# Control_Board.net
KiCad netlist of a schematic drawn in EAGLE
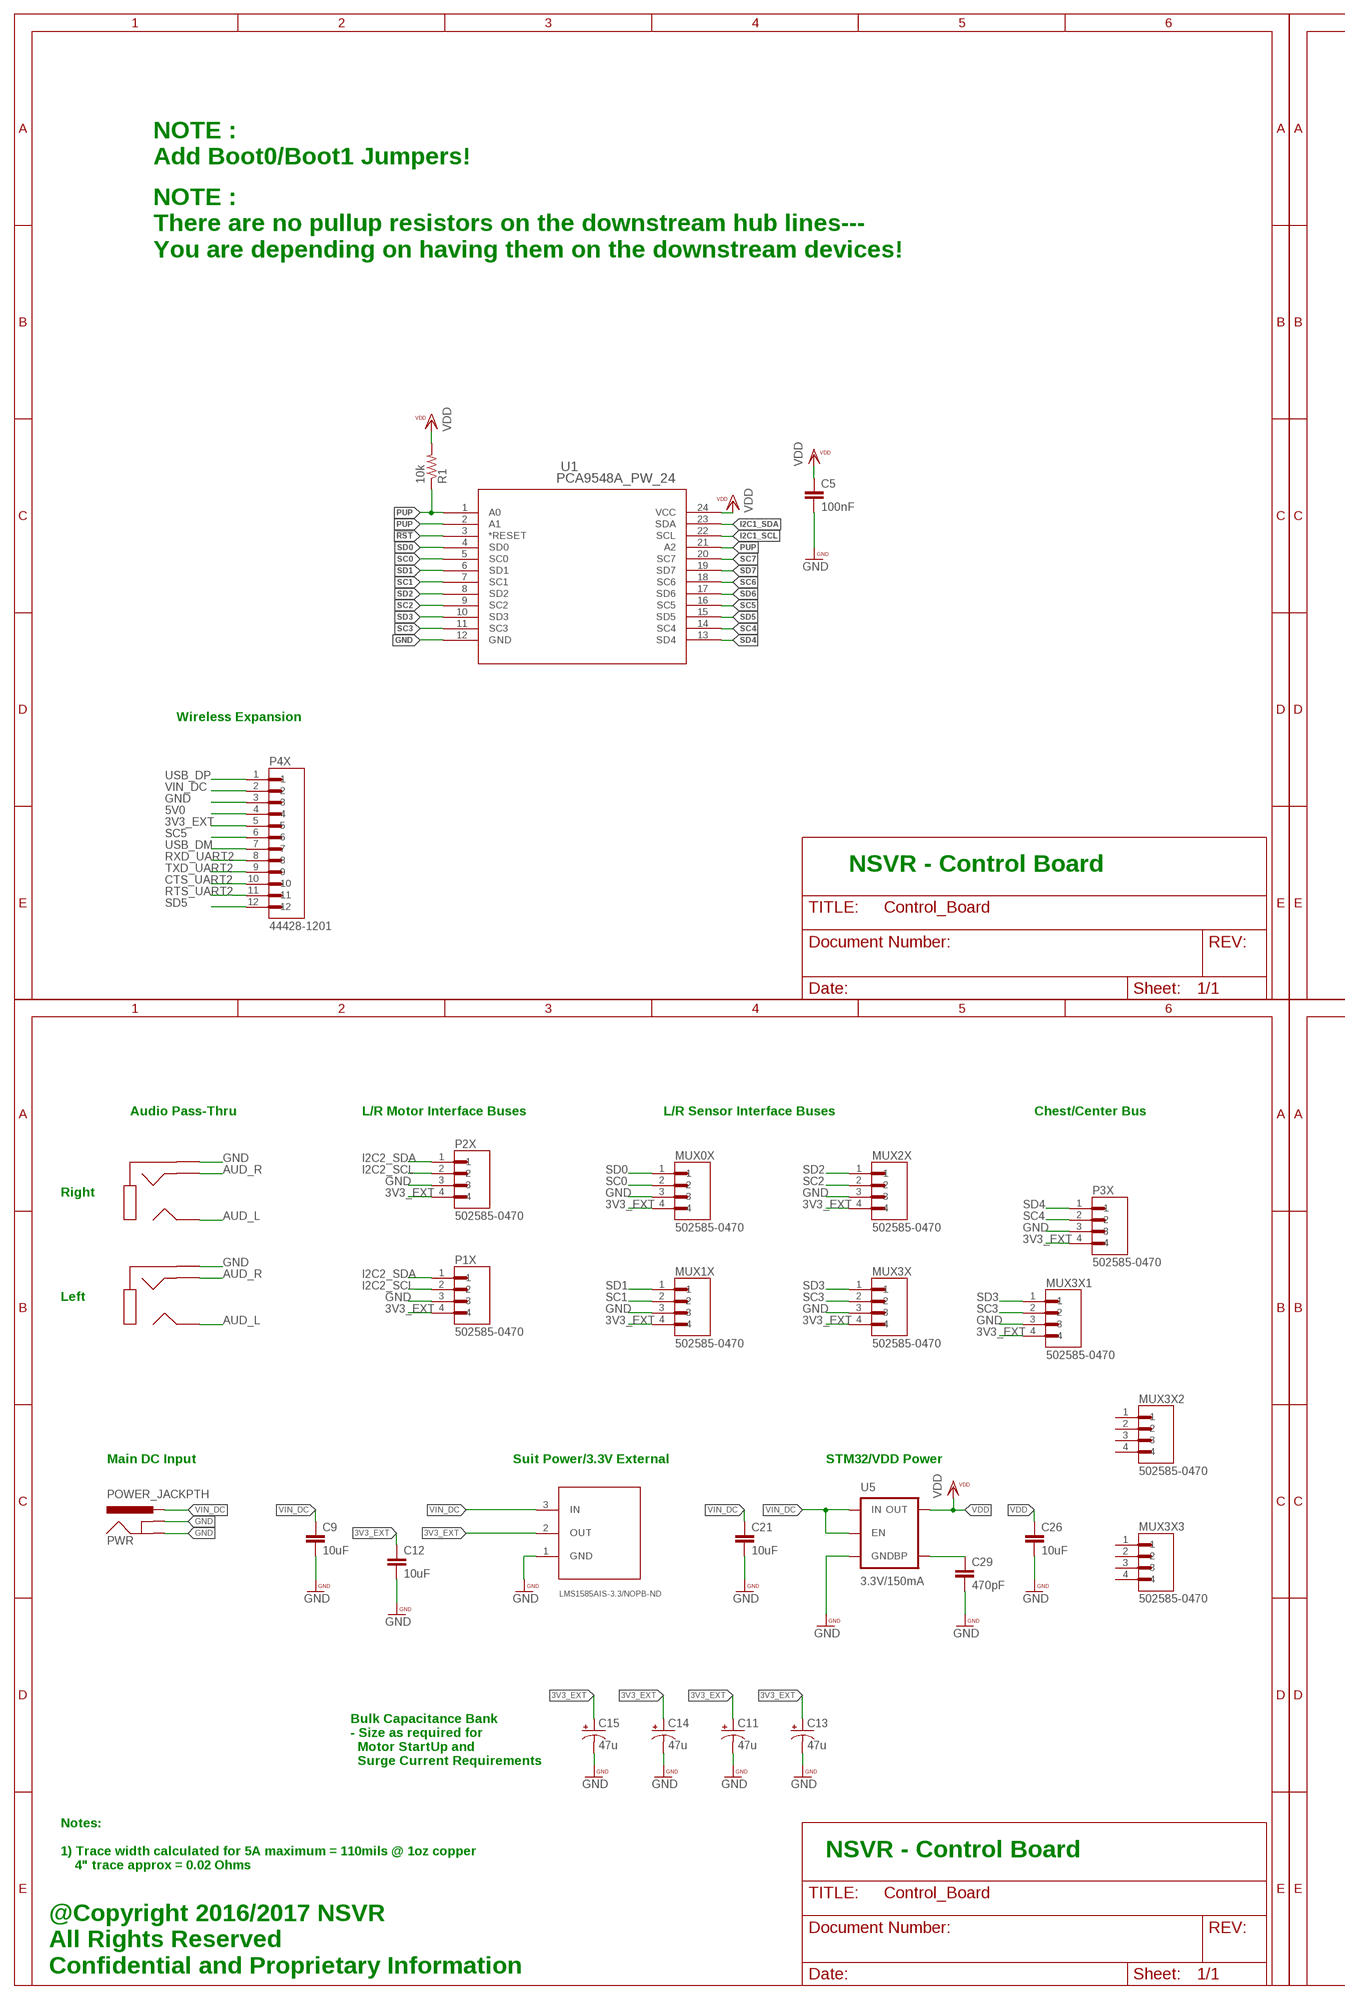
[diagram p0: schematic, sheet 1, part 1 of 2]
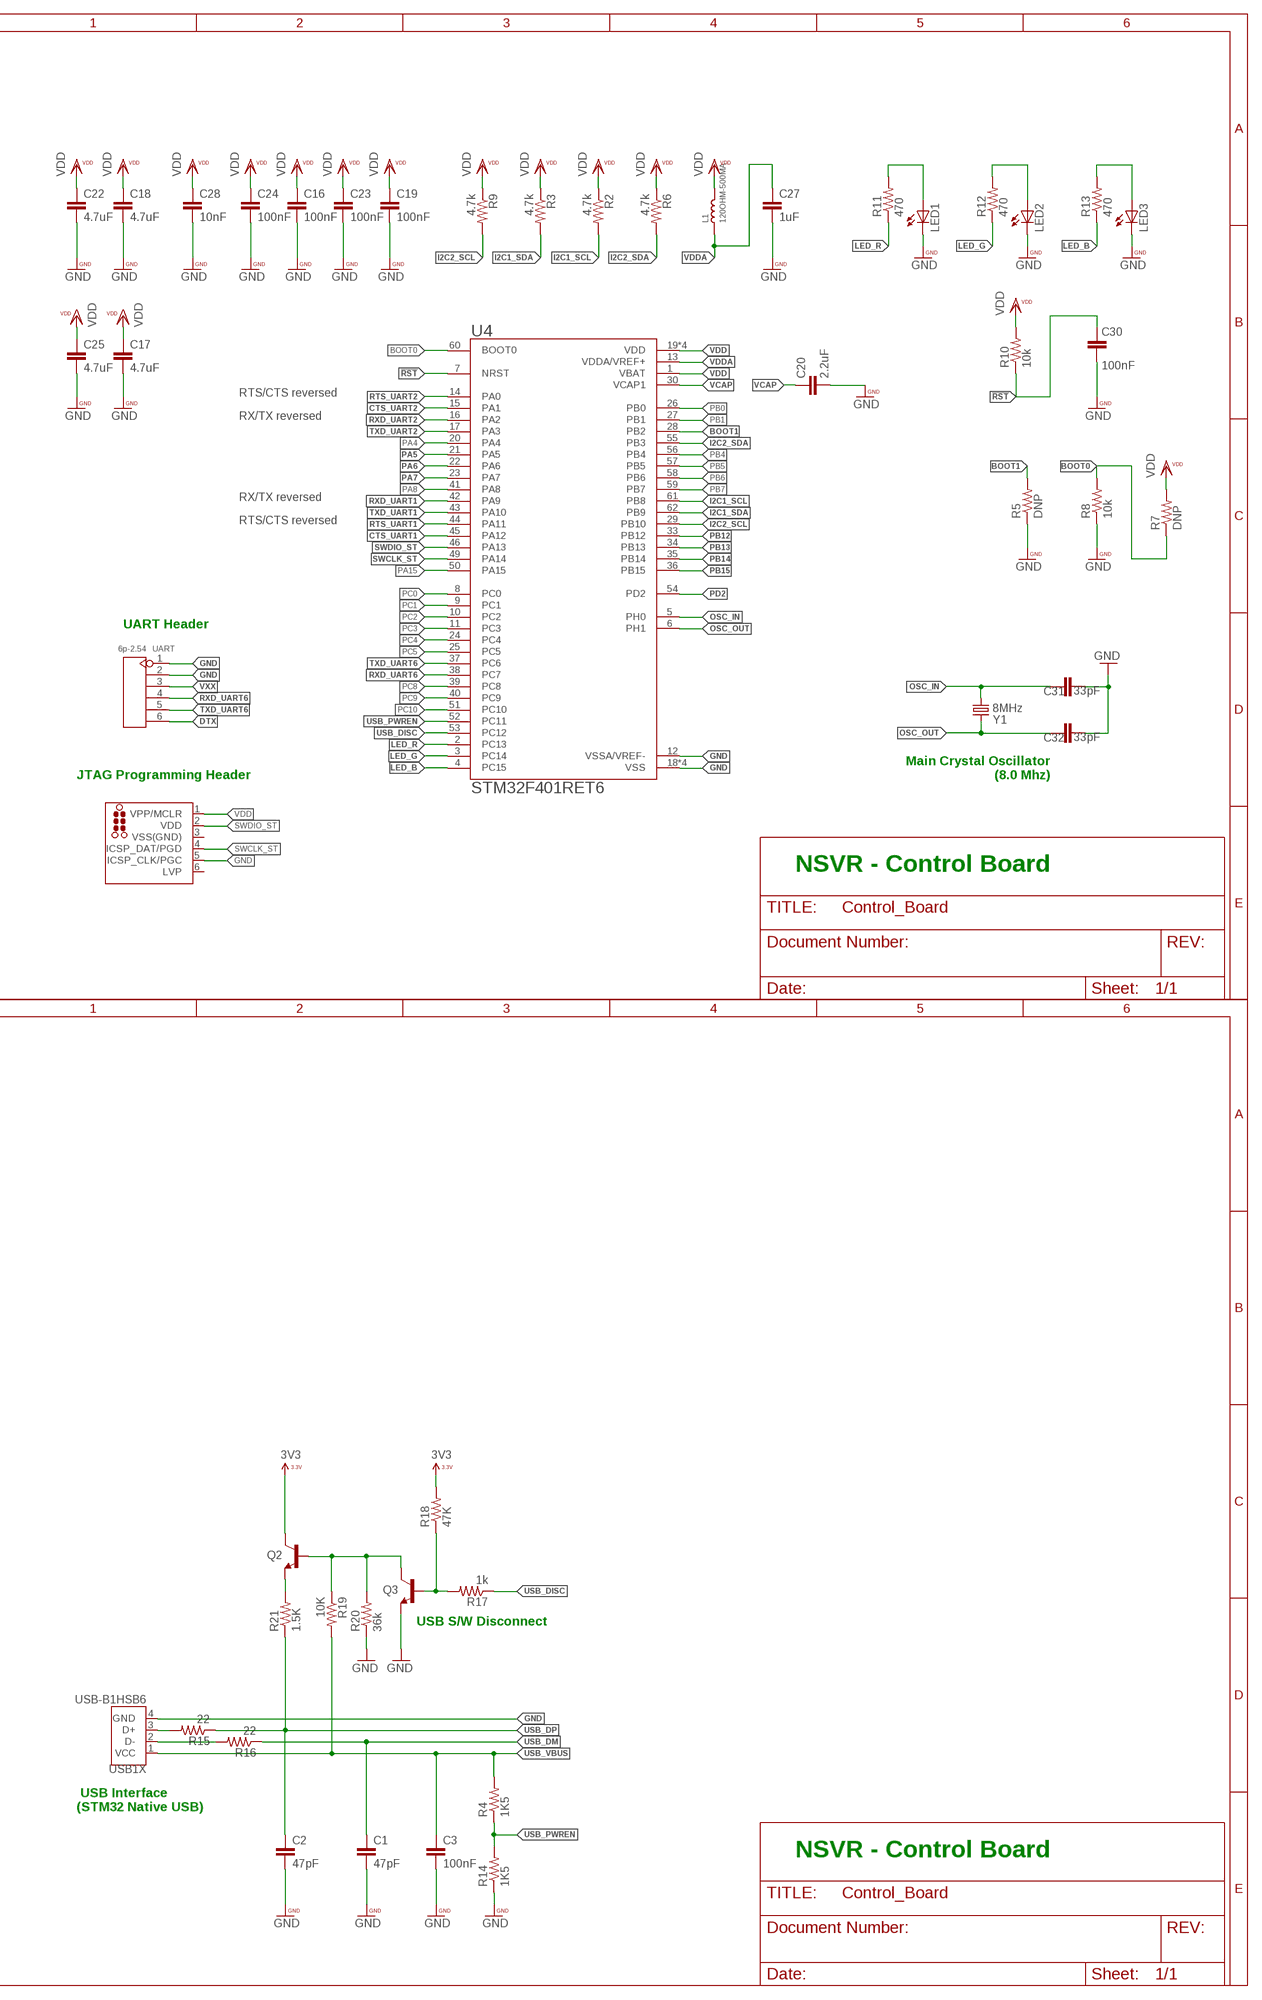
[diagram p1: schematic, sheet 1, part 2 of 2]

(export (version "E")
  (design (tool "Eeschema 10.0.6"))
  (components
    (comp (ref "C1")
      (value "47pF")
      (footprint "eagle-import:0402-CAP")
      (libsource (lib "eagle-import") (part "CAP0402-CAP"))
    )
    (comp (ref "C2")
      (value "47pF")
      (footprint "eagle-import:0402-CAP")
      (libsource (lib "eagle-import") (part "CAP0402-CAP"))
    )
    (comp (ref "C3")
      (value "100nF")
      (footprint "eagle-import:0402-CAP")
      (libsource (lib "eagle-import") (part "CAP0402-CAP"))
    )
    (comp (ref "C5")
      (value "100nF")
      (footprint "eagle-import:0402-CAP")
      (libsource (lib "eagle-import") (part "CAP0402-CAP"))
    )
    (comp (ref "C9")
      (value "10uF")
      (footprint "eagle-import:0603-CAP")
      (libsource (lib "eagle-import") (part "CAP0603-CAP"))
    )
    (comp (ref "C11")
      (value "47u")
      (footprint "eagle-import:PANASONIC_D")
      (libsource (lib "eagle-import") (part "CAP_POLD"))
    )
    (comp (ref "C12")
      (value "10uF")
      (footprint "eagle-import:0603-CAP")
      (libsource (lib "eagle-import") (part "CAP0603-CAP"))
    )
    (comp (ref "C13")
      (value "47u")
      (footprint "eagle-import:PANASONIC_D")
      (libsource (lib "eagle-import") (part "CAP_POLD"))
    )
    (comp (ref "C14")
      (value "47u")
      (footprint "eagle-import:PANASONIC_D")
      (libsource (lib "eagle-import") (part "CAP_POLD"))
    )
    (comp (ref "C15")
      (value "47u")
      (footprint "eagle-import:PANASONIC_D")
      (libsource (lib "eagle-import") (part "CAP_POLD"))
    )
    (comp (ref "C16")
      (value "100nF")
      (footprint "eagle-import:0402-CAP")
      (libsource (lib "eagle-import") (part "CAP0402-CAP"))
    )
    (comp (ref "C17")
      (value "4.7uF")
      (footprint "eagle-import:0402-CAP")
      (libsource (lib "eagle-import") (part "CAP0402-CAP"))
    )
    (comp (ref "C18")
      (value "4.7uF")
      (footprint "eagle-import:0402-CAP")
      (libsource (lib "eagle-import") (part "CAP0402-CAP"))
    )
    (comp (ref "C19")
      (value "100nF")
      (footprint "eagle-import:0402-CAP")
      (libsource (lib "eagle-import") (part "CAP0402-CAP"))
    )
    (comp (ref "C20")
      (value "2.2uF")
      (footprint "eagle-import:0402-CAP")
      (libsource (lib "eagle-import") (part "CAP0402-CAP"))
    )
    (comp (ref "C21")
      (value "10uF")
      (footprint "eagle-import:0603-CAP")
      (libsource (lib "eagle-import") (part "CAP0603-CAP"))
    )
    (comp (ref "C22")
      (value "4.7uF")
      (footprint "eagle-import:0402-CAP")
      (libsource (lib "eagle-import") (part "CAP0402-CAP"))
    )
    (comp (ref "C23")
      (value "100nF")
      (footprint "eagle-import:0402-CAP")
      (libsource (lib "eagle-import") (part "CAP0402-CAP"))
    )
    (comp (ref "C24")
      (value "100nF")
      (footprint "eagle-import:0402-CAP")
      (libsource (lib "eagle-import") (part "CAP0402-CAP"))
    )
    (comp (ref "C25")
      (value "4.7uF")
      (footprint "eagle-import:0402-CAP")
      (libsource (lib "eagle-import") (part "CAP0402-CAP"))
    )
    (comp (ref "C26")
      (value "10uF")
      (footprint "eagle-import:0603-CAP")
      (libsource (lib "eagle-import") (part "CAP0603-CAP"))
    )
    (comp (ref "C27")
      (value "1uF")
      (footprint "eagle-import:0402-CAP")
      (libsource (lib "eagle-import") (part "CAP0402-CAP"))
    )
    (comp (ref "C28")
      (value "10nF")
      (footprint "eagle-import:0402-CAP")
      (libsource (lib "eagle-import") (part "CAP0402-CAP"))
    )
    (comp (ref "C29")
      (value "470pF")
      (footprint "eagle-import:0402-CAP")
      (libsource (lib "eagle-import") (part "CAP0402-CAP"))
    )
    (comp (ref "C30")
      (value "100nF")
      (footprint "eagle-import:0402-CAP")
      (libsource (lib "eagle-import") (part "CAP0402-CAP"))
    )
    (comp (ref "C31")
      (value "33pF")
      (footprint "eagle-import:0402-CAP")
      (libsource (lib "eagle-import") (part "CAP0402-CAP"))
    )
    (comp (ref "C32")
      (value "33pF")
      (footprint "eagle-import:0402-CAP")
      (libsource (lib "eagle-import") (part "CAP0402-CAP"))
    )
    (comp (ref "J_ST")
      (value "TC2030-MCP-NL")
      (footprint "eagle-import:TC2030-MCP-NL")
      (libsource (lib "eagle-import") (part "TC2030-MCP-NL"))
    )
    (comp (ref "L1")
      (value "120OHM-500MA")
      (footprint "eagle-import:L0603")
      (fields (field (name "MPN") "BLM18AG121SN1D"))
      (libsource (lib "eagle-import") (part "SMD-FERRITE-CHIP-120-OHM-500MA(0603)"))
    )
    (comp (ref "LED1")
      (value "LEDCHIP-LED0603")
      (footprint "eagle-import:CHIP-LED0603")
      (libsource (lib "eagle-import") (part "LEDCHIP-LED0603"))
    )
    (comp (ref "LED2")
      (value "LEDCHIP-LED0603")
      (footprint "eagle-import:CHIP-LED0603")
      (libsource (lib "eagle-import") (part "LEDCHIP-LED0603"))
    )
    (comp (ref "LED3")
      (value "LEDCHIP-LED0603")
      (footprint "eagle-import:CHIP-LED0603")
      (libsource (lib "eagle-import") (part "LEDCHIP-LED0603"))
    )
    (comp (ref "MUX0X")
      (value "502585-0470")
      (footprint "eagle-import:MOLEX_502585-0470")
      (fields (field (name "MF") "Molex"))
      (libsource (lib "eagle-import") (part "502585-0470"))
    )
    (comp (ref "MUX1X")
      (value "502585-0470")
      (footprint "eagle-import:MOLEX_502585-0470")
      (fields (field (name "MF") "Molex"))
      (libsource (lib "eagle-import") (part "502585-0470"))
    )
    (comp (ref "MUX2X")
      (value "502585-0470")
      (footprint "eagle-import:MOLEX_502585-0470")
      (fields (field (name "MF") "Molex"))
      (libsource (lib "eagle-import") (part "502585-0470"))
    )
    (comp (ref "MUX3X")
      (value "502585-0470")
      (footprint "eagle-import:MOLEX_502585-0470")
      (fields (field (name "MF") "Molex"))
      (libsource (lib "eagle-import") (part "502585-0470"))
    )
    (comp (ref "MUX3X1")
      (value "502585-0470")
      (footprint "eagle-import:MOLEX_502585-0470")
      (fields (field (name "MF") "Molex"))
      (libsource (lib "eagle-import") (part "502585-0470"))
    )
    (comp (ref "MUX3X2")
      (value "502585-0470")
      (footprint "eagle-import:MOLEX_502585-0470")
      (fields (field (name "MF") "Molex"))
      (libsource (lib "eagle-import") (part "502585-0470"))
    )
    (comp (ref "MUX3X3")
      (value "502585-0470")
      (footprint "eagle-import:MOLEX_502585-0470")
      (fields (field (name "MF") "Molex"))
      (libsource (lib "eagle-import") (part "502585-0470"))
    )
    (comp (ref "P1X")
      (value "502585-0470")
      (footprint "eagle-import:MOLEX_502585-0470")
      (fields (field (name "MF") "Molex"))
      (libsource (lib "eagle-import") (part "502585-0470"))
    )
    (comp (ref "P2X")
      (value "502585-0470")
      (footprint "eagle-import:MOLEX_502585-0470")
      (fields (field (name "MF") "Molex"))
      (libsource (lib "eagle-import") (part "502585-0470"))
    )
    (comp (ref "P3X")
      (value "502585-0470")
      (footprint "eagle-import:MOLEX_502585-0470")
      (fields (field (name "MF") "Molex"))
      (libsource (lib "eagle-import") (part "502585-0470"))
    )
    (comp (ref "P4X")
      (value "44428-1201")
      (footprint "eagle-import:MOLEX_44428-1201")
      (fields (field (name "MF") "Molex"))
      (libsource (lib "eagle-import") (part "44428-1201"))
    )
    (comp (ref "PJ1")
      (value "SJ1-3513N")
      (footprint "eagle-import:SJ1-351XN")
      (libsource (lib "eagle-import") (part "SJ1-3513N"))
    )
    (comp (ref "PJ2")
      (value "SJ1-3513N")
      (footprint "eagle-import:SJ1-351XN")
      (libsource (lib "eagle-import") (part "SJ1-3513N"))
    )
    (comp (ref "PWR")
      (value "POWER_JACKPTH")
      (footprint "eagle-import:POWER_JACK_PTH")
      (libsource (lib "eagle-import") (part "POWER_JACKPTH"))
    )
    (comp (ref "Q2")
      (value "TRANSISTOR_NPNSOT23")
      (footprint "eagle-import:SOT23")
      (libsource (lib "eagle-import") (part "TRANSISTOR_NPNSOT23"))
    )
    (comp (ref "Q3")
      (value "TRANSISTOR_NPNSOT23")
      (footprint "eagle-import:SOT23")
      (libsource (lib "eagle-import") (part "TRANSISTOR_NPNSOT23"))
    )
    (comp (ref "R1")
      (value "10k")
      (footprint "eagle-import:EIA-0402")
      (libsource (lib "eagle-import") (part "RESISTOR0402-TYP"))
    )
    (comp (ref "R2")
      (value "4.7k")
      (footprint "eagle-import:EIA-0402")
      (libsource (lib "eagle-import") (part "RESISTOR0402-TYP"))
    )
    (comp (ref "R3")
      (value "4.7k")
      (footprint "eagle-import:EIA-0402")
      (libsource (lib "eagle-import") (part "RESISTOR0402-TYP"))
    )
    (comp (ref "R4")
      (value "1K5")
      (footprint "eagle-import:EIA-0402")
      (libsource (lib "eagle-import") (part "RESISTOR0402-TYP"))
    )
    (comp (ref "R5")
      (value "DNP")
      (footprint "eagle-import:EIA-0402")
      (libsource (lib "eagle-import") (part "RESISTOR0402-TYP"))
    )
    (comp (ref "R6")
      (value "4.7k")
      (footprint "eagle-import:EIA-0402")
      (libsource (lib "eagle-import") (part "RESISTOR0402-TYP"))
    )
    (comp (ref "R7")
      (value "DNP")
      (footprint "eagle-import:EIA-0402")
      (libsource (lib "eagle-import") (part "RESISTOR0402-TYP"))
    )
    (comp (ref "R8")
      (value "10k")
      (footprint "eagle-import:EIA-0402")
      (libsource (lib "eagle-import") (part "RESISTOR0402-TYP"))
    )
    (comp (ref "R9")
      (value "4.7k")
      (footprint "eagle-import:EIA-0402")
      (libsource (lib "eagle-import") (part "RESISTOR0402-TYP"))
    )
    (comp (ref "R10")
      (value "10k")
      (footprint "eagle-import:EIA-0402")
      (libsource (lib "eagle-import") (part "RESISTOR0402-TYP"))
    )
    (comp (ref "R11")
      (value "470")
      (footprint "eagle-import:EIA-0402")
      (libsource (lib "eagle-import") (part "RESISTOR0402-TYP"))
    )
    (comp (ref "R12")
      (value "470")
      (footprint "eagle-import:EIA-0402")
      (libsource (lib "eagle-import") (part "RESISTOR0402-TYP"))
    )
    (comp (ref "R13")
      (value "470")
      (footprint "eagle-import:EIA-0402")
      (libsource (lib "eagle-import") (part "RESISTOR0402-TYP"))
    )
    (comp (ref "R14")
      (value "1K5")
      (footprint "eagle-import:EIA-0402")
      (libsource (lib "eagle-import") (part "RESISTOR0402-TYP"))
    )
    (comp (ref "R15")
      (value "22")
      (footprint "eagle-import:EIA-0402")
      (libsource (lib "eagle-import") (part "RESISTOR0402-TYP"))
    )
    (comp (ref "R16")
      (value "22")
      (footprint "eagle-import:EIA-0402")
      (libsource (lib "eagle-import") (part "RESISTOR0402-TYP"))
    )
    (comp (ref "R17")
      (value "1k")
      (footprint "eagle-import:EIA-0402")
      (libsource (lib "eagle-import") (part "RESISTOR0402-TYP"))
    )
    (comp (ref "R18")
      (value "47K")
      (footprint "eagle-import:EIA-0402")
      (libsource (lib "eagle-import") (part "RESISTOR0402-TYP"))
    )
    (comp (ref "R19")
      (value "10K")
      (footprint "eagle-import:EIA-0402")
      (libsource (lib "eagle-import") (part "RESISTOR0402-TYP"))
    )
    (comp (ref "R20")
      (value "36k")
      (footprint "eagle-import:EIA-0402")
      (libsource (lib "eagle-import") (part "RESISTOR0402-TYP"))
    )
    (comp (ref "R21")
      (value "1.5K")
      (footprint "eagle-import:EIA-0402")
      (libsource (lib "eagle-import") (part "RESISTOR0402-TYP"))
    )
    (comp (ref "U1")
      (value "PCA9548A_PW_24")
      (footprint "eagle-import:PW24")
      (fields
        (field (name "GENERIC_PART_NUMBER") "PCA9548A")
        (field (name "MANUFACTURER") "Texas Instruments")
        (field (name "MANUFACTURER_PART_NUMBER") "pca9548a_pw_24")
      )
      (libsource (lib "eagle-import") (part "PCA9548A_PW_24"))
    )
    (comp (ref "U3")
      (value "LMS1585AIS-3.3/NOPB-ND")
      (footprint "eagle-import:TO254P1524X483-4N")
      (libsource (lib "eagle-import") (part "LMS1585AIS-3.3/NOPB-ND"))
    )
    (comp (ref "U4")
      (value "STM32F401RET6")
      (footprint "eagle-import:QFP50P1200X1200X160-64N")
      (fields (field (name "MF") "STMicroelectronics"))
      (libsource (lib "eagle-import") (part "STM32F401RET6"))
    )
    (comp (ref "U5")
      (value "3.3V/150mA")
      (footprint "eagle-import:SOT23-5")
      (libsource (lib "eagle-import") (part "V_REG_MIC52053.3V"))
    )
    (comp (ref "UART")
      (value "6p-2.54")
      (footprint "eagle-import:H6-2.54")
      (fields (field (name "MPN") "F185-1106A1BSYC1"))
      (libsource (lib "eagle-import") (part "DIP-BLACK-FEMALE-HEADER-VERT(6P-2.54)"))
    )
    (comp (ref "USB1X")
      (value "USB-B1HSB6")
      (footprint "eagle-import:OST_USB-B1HSB6")
      (fields (field (name "MF") "On Shore Technology"))
      (libsource (lib "eagle-import") (part "USB-B1HSB6"))
    )
    (comp (ref "Y1")
      (value "8MHz")
      (footprint "eagle-import:CRYSTAL-SMD-5X3")
      (libsource (lib "eagle-import") (part "CRYSTAL5X3"))
    )
  )
  (nets
    (net (code "1") (name "/5V0") (class "Default")
      (node (ref "P4X") (pin "4") (pinfunction "4_4") (pintype "passive"))
    )
    (net (code "2") (name "/AUD_L") (class "Default")
      (node (ref "PJ1") (pin "2") (pinfunction "2_2") (pintype "bidirectional"))
      (node (ref "PJ2") (pin "2") (pinfunction "2_2") (pintype "bidirectional"))
    )
    (net (code "3") (name "/AUD_R") (class "Default")
      (node (ref "PJ1") (pin "3") (pinfunction "3_3") (pintype "bidirectional"))
      (node (ref "PJ2") (pin "3") (pinfunction "3_3") (pintype "bidirectional"))
    )
    (net (code "4") (name "/VSS(GND)") (class "Default")
      (node (ref "J_ST") (pin "3") (pinfunction "VSS(GND)_3") (pintype "power_in"))
    )
    (net (code "5") (name "/~{RST}") (class "Default")
      (node (ref "C30") (pin "1") (pinfunction "1_1") (pintype "passive"))
      (node (ref "R10") (pin "1") (pinfunction "1_1") (pintype "passive"))
      (node (ref "U1") (pin "3") (pinfunction "*RESET_3") (pintype "input"))
      (node (ref "U4") (pin "7") (pinfunction "NRST_7") (pintype "bidirectional"))
    )
    (net (code "6") (name "3V3") (class "Default")
      (node (ref "Q2") (pin "3") (pinfunction "C_3") (pintype "passive"))
      (node (ref "R18") (pin "2") (pinfunction "2_2") (pintype "passive"))
    )
    (net (code "7") (name "3V3_EXT") (class "Default")
      (node (ref "C11") (pin "+") (pinfunction "+_+") (pintype "passive"))
      (node (ref "C12") (pin "1") (pinfunction "1_1") (pintype "passive"))
      (node (ref "C13") (pin "+") (pinfunction "+_+") (pintype "passive"))
      (node (ref "C14") (pin "+") (pinfunction "+_+") (pintype "passive"))
      (node (ref "C15") (pin "+") (pinfunction "+_+") (pintype "passive"))
      (node (ref "MUX0X") (pin "4") (pinfunction "4_4") (pintype "passive"))
      (node (ref "MUX1X") (pin "4") (pinfunction "4_4") (pintype "passive"))
      (node (ref "MUX2X") (pin "4") (pinfunction "4_4") (pintype "passive"))
      (node (ref "MUX3X") (pin "4") (pinfunction "4_4") (pintype "passive"))
      (node (ref "MUX3X1") (pin "4") (pinfunction "4_4") (pintype "passive"))
      (node (ref "P1X") (pin "4") (pinfunction "4_4") (pintype "passive"))
      (node (ref "P2X") (pin "4") (pinfunction "4_4") (pintype "passive"))
      (node (ref "P3X") (pin "4") (pinfunction "4_4") (pintype "passive"))
      (node (ref "P4X") (pin "5") (pinfunction "5_5") (pintype "passive"))
      (node (ref "U3") (pin "2") (pinfunction "OUT_2") (pintype "bidirectional"))
    )
    (net (code "8") (name "BOOT0") (class "Default")
      (node (ref "R7") (pin "1") (pinfunction "1_1") (pintype "passive"))
      (node (ref "R8") (pin "2") (pinfunction "2_2") (pintype "passive"))
      (node (ref "U4") (pin "60") (pinfunction "BOOT0_60") (pintype "input"))
    )
    (net (code "9") (name "BOOT1") (class "Default")
      (node (ref "R5") (pin "2") (pinfunction "2_2") (pintype "passive"))
      (node (ref "U4") (pin "28") (pinfunction "PB2_28") (pintype "bidirectional"))
    )
    (net (code "10") (name "CTS_UART1") (class "Default")
      (node (ref "U4") (pin "45") (pinfunction "PA12_45") (pintype "bidirectional"))
    )
    (net (code "11") (name "CTS_UART2") (class "Default")
      (node (ref "P4X") (pin "10") (pinfunction "10_10") (pintype "passive"))
      (node (ref "U4") (pin "15") (pinfunction "PA1_15") (pintype "bidirectional"))
    )
    (net (code "12") (name "DTX") (class "Default")
      (node (ref "UART") (pin "6") (pinfunction "6_6") (pintype "bidirectional"))
    )
    (net (code "13") (name "GND") (class "Default")
      (node (ref "C1") (pin "2") (pinfunction "2_2") (pintype "passive"))
      (node (ref "C11") (pin "-") (pinfunction "-_-") (pintype "passive"))
      (node (ref "C12") (pin "2") (pinfunction "2_2") (pintype "passive"))
      (node (ref "C13") (pin "-") (pinfunction "-_-") (pintype "passive"))
      (node (ref "C14") (pin "-") (pinfunction "-_-") (pintype "passive"))
      (node (ref "C15") (pin "-") (pinfunction "-_-") (pintype "passive"))
      (node (ref "C16") (pin "2") (pinfunction "2_2") (pintype "passive"))
      (node (ref "C17") (pin "2") (pinfunction "2_2") (pintype "passive"))
      (node (ref "C18") (pin "2") (pinfunction "2_2") (pintype "passive"))
      (node (ref "C19") (pin "2") (pinfunction "2_2") (pintype "passive"))
      (node (ref "C2") (pin "2") (pinfunction "2_2") (pintype "passive"))
      (node (ref "C20") (pin "2") (pinfunction "2_2") (pintype "passive"))
      (node (ref "C21") (pin "2") (pinfunction "2_2") (pintype "passive"))
      (node (ref "C22") (pin "2") (pinfunction "2_2") (pintype "passive"))
      (node (ref "C23") (pin "2") (pinfunction "2_2") (pintype "passive"))
      (node (ref "C24") (pin "2") (pinfunction "2_2") (pintype "passive"))
      (node (ref "C25") (pin "2") (pinfunction "2_2") (pintype "passive"))
      (node (ref "C26") (pin "2") (pinfunction "2_2") (pintype "passive"))
      (node (ref "C27") (pin "2") (pinfunction "2_2") (pintype "passive"))
      (node (ref "C28") (pin "2") (pinfunction "2_2") (pintype "passive"))
      (node (ref "C29") (pin "2") (pinfunction "2_2") (pintype "passive"))
      (node (ref "C3") (pin "2") (pinfunction "2_2") (pintype "passive"))
      (node (ref "C30") (pin "2") (pinfunction "2_2") (pintype "passive"))
      (node (ref "C31") (pin "1") (pinfunction "1_1") (pintype "passive"))
      (node (ref "C32") (pin "1") (pinfunction "1_1") (pintype "passive"))
      (node (ref "C5") (pin "2") (pinfunction "2_2") (pintype "passive"))
      (node (ref "C9") (pin "2") (pinfunction "2_2") (pintype "passive"))
      (node (ref "J_ST") (pin "5") (pinfunction "ICSP_CLK/PGC_5") (pintype "output"))
      (node (ref "LED1") (pin "C") (pinfunction "C_C") (pintype "passive"))
      (node (ref "LED2") (pin "C") (pinfunction "C_C") (pintype "passive"))
      (node (ref "LED3") (pin "C") (pinfunction "C_C") (pintype "passive"))
      (node (ref "MUX0X") (pin "3") (pinfunction "3_3") (pintype "passive"))
      (node (ref "MUX1X") (pin "3") (pinfunction "3_3") (pintype "passive"))
      (node (ref "MUX2X") (pin "3") (pinfunction "3_3") (pintype "passive"))
      (node (ref "MUX3X") (pin "3") (pinfunction "3_3") (pintype "passive"))
      (node (ref "MUX3X1") (pin "3") (pinfunction "3_3") (pintype "passive"))
      (node (ref "P1X") (pin "3") (pinfunction "3_3") (pintype "passive"))
      (node (ref "P2X") (pin "3") (pinfunction "3_3") (pintype "passive"))
      (node (ref "P3X") (pin "3") (pinfunction "3_3") (pintype "passive"))
      (node (ref "P4X") (pin "3") (pinfunction "3_3") (pintype "passive"))
      (node (ref "PJ1") (pin "1") (pinfunction "1_1") (pintype "bidirectional"))
      (node (ref "PJ2") (pin "1") (pinfunction "1_1") (pintype "bidirectional"))
      (node (ref "PWR") (pin "GND") (pinfunction "GND_GND") (pintype "bidirectional"))
      (node (ref "PWR") (pin "GNDBREAK") (pinfunction "GNDBREAK_GNDBREAK") (pintype "bidirectional"))
      (node (ref "Q3") (pin "2") (pinfunction "E_2") (pintype "passive"))
      (node (ref "R14") (pin "1") (pinfunction "1_1") (pintype "passive"))
      (node (ref "R20") (pin "1") (pinfunction "1_1") (pintype "passive"))
      (node (ref "R5") (pin "1") (pinfunction "1_1") (pintype "passive"))
      (node (ref "R8") (pin "1") (pinfunction "1_1") (pintype "passive"))
      (node (ref "U1") (pin "12") (pinfunction "GND_12") (pintype "power_in"))
      (node (ref "U3") (pin "1") (pinfunction "GND_1") (pintype "bidirectional"))
      (node (ref "U4") (pin "12") (pinfunction "VSSA/VREF-_12") (pintype "power_in"))
      (node (ref "U4") (pin "18") (pinfunction "VSS_18") (pintype "power_in"))
      (node (ref "U4") (pin "31") (pinfunction "VSS_31") (pintype "power_in"))
      (node (ref "U4") (pin "47") (pinfunction "VSS_47") (pintype "power_in"))
      (node (ref "U4") (pin "63") (pinfunction "VSS_63") (pintype "power_in"))
      (node (ref "U5") (pin "2") (pinfunction "GND_2") (pintype "input"))
      (node (ref "UART") (pin "1") (pinfunction "1_1") (pintype "bidirectional"))
      (node (ref "UART") (pin "2") (pinfunction "2_2") (pintype "bidirectional"))
      (node (ref "USB1X") (pin "4") (pinfunction "GND_4") (pintype "power_in"))
    )
    (net (code "14") (name "I2C1_SCL") (class "Default")
      (node (ref "R2") (pin "2") (pinfunction "2_2") (pintype "passive"))
      (node (ref "U1") (pin "22") (pinfunction "SCL_22") (pintype "passive"))
      (node (ref "U4") (pin "61") (pinfunction "PB8_61") (pintype "bidirectional"))
    )
    (net (code "15") (name "I2C1_SDA") (class "Default")
      (node (ref "R3") (pin "2") (pinfunction "2_2") (pintype "passive"))
      (node (ref "U1") (pin "23") (pinfunction "SDA_23") (pintype "passive"))
      (node (ref "U4") (pin "62") (pinfunction "PB9_62") (pintype "bidirectional"))
    )
    (net (code "16") (name "I2C2_SCL") (class "Default")
      (node (ref "P1X") (pin "2") (pinfunction "2_2") (pintype "passive"))
      (node (ref "P2X") (pin "2") (pinfunction "2_2") (pintype "passive"))
      (node (ref "R9") (pin "2") (pinfunction "2_2") (pintype "passive"))
      (node (ref "U4") (pin "29") (pinfunction "PB10_29") (pintype "bidirectional"))
    )
    (net (code "17") (name "I2C2_SDA") (class "Default")
      (node (ref "P1X") (pin "1") (pinfunction "1_1") (pintype "passive"))
      (node (ref "P2X") (pin "1") (pinfunction "1_1") (pintype "passive"))
      (node (ref "R6") (pin "2") (pinfunction "2_2") (pintype "passive"))
      (node (ref "U4") (pin "55") (pinfunction "PB3_55") (pintype "bidirectional"))
    )
    (net (code "18") (name "LED_B") (class "Default")
      (node (ref "R13") (pin "1") (pinfunction "1_1") (pintype "passive"))
      (node (ref "U4") (pin "4") (pinfunction "PC15_4") (pintype "bidirectional"))
    )
    (net (code "19") (name "LED_G") (class "Default")
      (node (ref "R12") (pin "1") (pinfunction "1_1") (pintype "passive"))
      (node (ref "U4") (pin "3") (pinfunction "PC14_3") (pintype "bidirectional"))
    )
    (net (code "20") (name "LED_R") (class "Default")
      (node (ref "R11") (pin "1") (pinfunction "1_1") (pintype "passive"))
      (node (ref "U4") (pin "2") (pinfunction "PC13_2") (pintype "bidirectional"))
    )
    (net (code "21") (name "Net-(LED1-PadA)") (class "Default")
      (node (ref "LED1") (pin "A") (pinfunction "A_A") (pintype "passive"))
      (node (ref "R11") (pin "2") (pinfunction "2_2") (pintype "passive"))
    )
    (net (code "22") (name "Net-(LED2-PadA)") (class "Default")
      (node (ref "LED2") (pin "A") (pinfunction "A_A") (pintype "passive"))
      (node (ref "R12") (pin "2") (pinfunction "2_2") (pintype "passive"))
    )
    (net (code "23") (name "Net-(LED3-PadA)") (class "Default")
      (node (ref "LED3") (pin "A") (pinfunction "A_A") (pintype "passive"))
      (node (ref "R13") (pin "2") (pinfunction "2_2") (pintype "passive"))
    )
    (net (code "24") (name "Net-(Q2-B)") (class "Default")
      (node (ref "Q2") (pin "1") (pinfunction "B_1") (pintype "passive"))
      (node (ref "Q3") (pin "3") (pinfunction "C_3") (pintype "passive"))
      (node (ref "R19") (pin "1") (pinfunction "1_1") (pintype "passive"))
      (node (ref "R20") (pin "2") (pinfunction "2_2") (pintype "passive"))
    )
    (net (code "25") (name "Net-(Q2-E)") (class "Default")
      (node (ref "Q2") (pin "2") (pinfunction "E_2") (pintype "passive"))
      (node (ref "R21") (pin "2") (pinfunction "2_2") (pintype "passive"))
    )
    (net (code "26") (name "Net-(Q3-B)") (class "Default")
      (node (ref "Q3") (pin "1") (pinfunction "B_1") (pintype "passive"))
      (node (ref "R17") (pin "2") (pinfunction "2_2") (pintype "passive"))
      (node (ref "R18") (pin "1") (pinfunction "1_1") (pintype "passive"))
    )
    (net (code "27") (name "Net-(U5-BP)") (class "Default")
      (node (ref "C29") (pin "1") (pinfunction "1_1") (pintype "passive"))
      (node (ref "U5") (pin "4") (pinfunction "BP_4") (pintype "input"))
    )
    (net (code "28") (name "Net-(USB1X-D+)") (class "Default")
      (node (ref "R15") (pin "2") (pinfunction "2_2") (pintype "passive"))
      (node (ref "USB1X") (pin "3") (pinfunction "D+_3") (pintype "bidirectional"))
    )
    (net (code "29") (name "Net-(USB1X-D-)") (class "Default")
      (node (ref "R16") (pin "2") (pinfunction "2_2") (pintype "passive"))
      (node (ref "USB1X") (pin "2") (pinfunction "D-_2") (pintype "bidirectional"))
    )
    (net (code "30") (name "OSC_IN") (class "Default")
      (node (ref "C31") (pin "2") (pinfunction "2_2") (pintype "passive"))
      (node (ref "U4") (pin "5") (pinfunction "PH0_5") (pintype "bidirectional"))
      (node (ref "Y1") (pin "1") (pinfunction "1_1") (pintype "passive"))
    )
    (net (code "31") (name "OSC_OUT") (class "Default")
      (node (ref "C32") (pin "2") (pinfunction "2_2") (pintype "passive"))
      (node (ref "U4") (pin "6") (pinfunction "PH1_6") (pintype "bidirectional"))
      (node (ref "Y1") (pin "3") (pinfunction "2_3") (pintype "passive"))
    )
    (net (code "32") (name "PA4") (class "Default")
      (node (ref "U4") (pin "20") (pinfunction "PA4_20") (pintype "bidirectional"))
    )
    (net (code "33") (name "PA5") (class "Default")
      (node (ref "U4") (pin "21") (pinfunction "PA5_21") (pintype "bidirectional"))
    )
    (net (code "34") (name "PA6") (class "Default")
      (node (ref "U4") (pin "22") (pinfunction "PA6_22") (pintype "bidirectional"))
    )
    (net (code "35") (name "PA7") (class "Default")
      (node (ref "U4") (pin "23") (pinfunction "PA7_23") (pintype "bidirectional"))
    )
    (net (code "36") (name "PA8") (class "Default")
      (node (ref "U4") (pin "41") (pinfunction "PA8_41") (pintype "bidirectional"))
    )
    (net (code "37") (name "PA15") (class "Default")
      (node (ref "U4") (pin "50") (pinfunction "PA15_50") (pintype "bidirectional"))
    )
    (net (code "38") (name "PB0") (class "Default")
      (node (ref "U4") (pin "26") (pinfunction "PB0_26") (pintype "bidirectional"))
    )
    (net (code "39") (name "PB1") (class "Default")
      (node (ref "U4") (pin "27") (pinfunction "PB1_27") (pintype "bidirectional"))
    )
    (net (code "40") (name "PB4") (class "Default")
      (node (ref "U4") (pin "56") (pinfunction "PB4_56") (pintype "bidirectional"))
    )
    (net (code "41") (name "PB5") (class "Default")
      (node (ref "U4") (pin "57") (pinfunction "PB5_57") (pintype "bidirectional"))
    )
    (net (code "42") (name "PB6") (class "Default")
      (node (ref "U4") (pin "58") (pinfunction "PB6_58") (pintype "bidirectional"))
    )
    (net (code "43") (name "PB7") (class "Default")
      (node (ref "U4") (pin "59") (pinfunction "PB7_59") (pintype "bidirectional"))
    )
    (net (code "44") (name "PB12") (class "Default")
      (node (ref "U4") (pin "33") (pinfunction "PB12_33") (pintype "bidirectional"))
    )
    (net (code "45") (name "PB13") (class "Default")
      (node (ref "U4") (pin "34") (pinfunction "PB13_34") (pintype "bidirectional"))
    )
    (net (code "46") (name "PB14") (class "Default")
      (node (ref "U4") (pin "35") (pinfunction "PB14_35") (pintype "bidirectional"))
    )
    (net (code "47") (name "PB15") (class "Default")
      (node (ref "U4") (pin "36") (pinfunction "PB15_36") (pintype "bidirectional"))
    )
    (net (code "48") (name "PC0") (class "Default")
      (node (ref "U4") (pin "8") (pinfunction "PC0_8") (pintype "bidirectional"))
    )
    (net (code "49") (name "PC1") (class "Default")
      (node (ref "U4") (pin "9") (pinfunction "PC1_9") (pintype "bidirectional"))
    )
    (net (code "50") (name "PC2") (class "Default")
      (node (ref "U4") (pin "10") (pinfunction "PC2_10") (pintype "bidirectional"))
    )
    (net (code "51") (name "PC3") (class "Default")
      (node (ref "U4") (pin "11") (pinfunction "PC3_11") (pintype "bidirectional"))
    )
    (net (code "52") (name "PC4") (class "Default")
      (node (ref "U4") (pin "24") (pinfunction "PC4_24") (pintype "bidirectional"))
    )
    (net (code "53") (name "PC5") (class "Default")
      (node (ref "U4") (pin "25") (pinfunction "PC5_25") (pintype "bidirectional"))
    )
    (net (code "54") (name "PC8") (class "Default")
      (node (ref "U4") (pin "39") (pinfunction "PC8_39") (pintype "bidirectional"))
    )
    (net (code "55") (name "PC9") (class "Default")
      (node (ref "U4") (pin "40") (pinfunction "PC9_40") (pintype "bidirectional"))
    )
    (net (code "56") (name "PC10") (class "Default")
      (node (ref "U4") (pin "51") (pinfunction "PC10_51") (pintype "bidirectional"))
    )
    (net (code "57") (name "PD2") (class "Default")
      (node (ref "U4") (pin "54") (pinfunction "PD2_54") (pintype "bidirectional"))
    )
    (net (code "58") (name "PUP") (class "Default")
      (node (ref "R1") (pin "1") (pinfunction "1_1") (pintype "passive"))
      (node (ref "U1") (pin "1") (pinfunction "A0_1") (pintype "input"))
      (node (ref "U1") (pin "2") (pinfunction "A1_2") (pintype "input"))
      (node (ref "U1") (pin "21") (pinfunction "A2_21") (pintype "input"))
    )
    (net (code "59") (name "RTS_UART1") (class "Default")
      (node (ref "U4") (pin "44") (pinfunction "PA11_44") (pintype "bidirectional"))
    )
    (net (code "60") (name "RTS_UART2") (class "Default")
      (node (ref "P4X") (pin "11") (pinfunction "11_11") (pintype "passive"))
      (node (ref "U4") (pin "14") (pinfunction "PA0_14") (pintype "bidirectional"))
    )
    (net (code "61") (name "RXD_UART1") (class "Default")
      (node (ref "U4") (pin "42") (pinfunction "PA9_42") (pintype "bidirectional"))
    )
    (net (code "62") (name "RXD_UART2") (class "Default")
      (node (ref "P4X") (pin "8") (pinfunction "8_8") (pintype "passive"))
      (node (ref "U4") (pin "16") (pinfunction "PA2_16") (pintype "bidirectional"))
    )
    (net (code "63") (name "RXD_UART6") (class "Default")
      (node (ref "U4") (pin "38") (pinfunction "PC7_38") (pintype "bidirectional"))
      (node (ref "UART") (pin "4") (pinfunction "4_4") (pintype "bidirectional"))
    )
    (net (code "64") (name "SC0") (class "Default")
      (node (ref "MUX0X") (pin "2") (pinfunction "2_2") (pintype "passive"))
      (node (ref "U1") (pin "5") (pinfunction "SC0_5") (pintype "passive"))
    )
    (net (code "65") (name "SC1") (class "Default")
      (node (ref "MUX1X") (pin "2") (pinfunction "2_2") (pintype "passive"))
      (node (ref "U1") (pin "7") (pinfunction "SC1_7") (pintype "passive"))
    )
    (net (code "66") (name "SC2") (class "Default")
      (node (ref "MUX2X") (pin "2") (pinfunction "2_2") (pintype "passive"))
      (node (ref "U1") (pin "9") (pinfunction "SC2_9") (pintype "passive"))
    )
    (net (code "67") (name "SC3") (class "Default")
      (node (ref "MUX3X") (pin "2") (pinfunction "2_2") (pintype "passive"))
      (node (ref "MUX3X1") (pin "2") (pinfunction "2_2") (pintype "passive"))
      (node (ref "U1") (pin "11") (pinfunction "SC3_11") (pintype "passive"))
    )
    (net (code "68") (name "SC4") (class "Default")
      (node (ref "P3X") (pin "2") (pinfunction "2_2") (pintype "passive"))
      (node (ref "U1") (pin "14") (pinfunction "SC4_14") (pintype "passive"))
    )
    (net (code "69") (name "SC5") (class "Default")
      (node (ref "P4X") (pin "6") (pinfunction "6_6") (pintype "passive"))
      (node (ref "U1") (pin "16") (pinfunction "SC5_16") (pintype "passive"))
    )
    (net (code "70") (name "SC6") (class "Default")
      (node (ref "U1") (pin "18") (pinfunction "SC6_18") (pintype "passive"))
    )
    (net (code "71") (name "SC7") (class "Default")
      (node (ref "U1") (pin "20") (pinfunction "SC7_20") (pintype "passive"))
    )
    (net (code "72") (name "SD0") (class "Default")
      (node (ref "MUX0X") (pin "1") (pinfunction "1_1") (pintype "passive"))
      (node (ref "U1") (pin "4") (pinfunction "SD0_4") (pintype "passive"))
    )
    (net (code "73") (name "SD1") (class "Default")
      (node (ref "MUX1X") (pin "1") (pinfunction "1_1") (pintype "passive"))
      (node (ref "U1") (pin "6") (pinfunction "SD1_6") (pintype "passive"))
    )
    (net (code "74") (name "SD2") (class "Default")
      (node (ref "MUX2X") (pin "1") (pinfunction "1_1") (pintype "passive"))
      (node (ref "U1") (pin "8") (pinfunction "SD2_8") (pintype "passive"))
    )
    (net (code "75") (name "SD3") (class "Default")
      (node (ref "MUX3X") (pin "1") (pinfunction "1_1") (pintype "passive"))
      (node (ref "MUX3X1") (pin "1") (pinfunction "1_1") (pintype "passive"))
      (node (ref "U1") (pin "10") (pinfunction "SD3_10") (pintype "passive"))
    )
    (net (code "76") (name "SD4") (class "Default")
      (node (ref "P3X") (pin "1") (pinfunction "1_1") (pintype "passive"))
      (node (ref "U1") (pin "13") (pinfunction "SD4_13") (pintype "passive"))
    )
    (net (code "77") (name "SD5") (class "Default")
      (node (ref "P4X") (pin "12") (pinfunction "12_12") (pintype "passive"))
      (node (ref "U1") (pin "15") (pinfunction "SD5_15") (pintype "passive"))
    )
    (net (code "78") (name "SD6") (class "Default")
      (node (ref "U1") (pin "17") (pinfunction "SD6_17") (pintype "passive"))
    )
    (net (code "79") (name "SD7") (class "Default")
      (node (ref "U1") (pin "19") (pinfunction "SD7_19") (pintype "passive"))
    )
    (net (code "80") (name "SWCLK_ST") (class "Default")
      (node (ref "J_ST") (pin "4") (pinfunction "ICSP_DAT/PGD_4") (pintype "bidirectional"))
      (node (ref "U4") (pin "49") (pinfunction "PA14_49") (pintype "bidirectional"))
    )
    (net (code "81") (name "SWDIO_ST") (class "Default")
      (node (ref "J_ST") (pin "2") (pinfunction "VDD_2") (pintype "power_in"))
      (node (ref "U4") (pin "46") (pinfunction "PA13_46") (pintype "bidirectional"))
    )
    (net (code "82") (name "TXD_UART1") (class "Default")
      (node (ref "U4") (pin "43") (pinfunction "PA10_43") (pintype "bidirectional"))
    )
    (net (code "83") (name "TXD_UART2") (class "Default")
      (node (ref "P4X") (pin "9") (pinfunction "9_9") (pintype "passive"))
      (node (ref "U4") (pin "17") (pinfunction "PA3_17") (pintype "bidirectional"))
    )
    (net (code "84") (name "TXD_UART6") (class "Default")
      (node (ref "U4") (pin "37") (pinfunction "PC6_37") (pintype "bidirectional"))
      (node (ref "UART") (pin "5") (pinfunction "5_5") (pintype "bidirectional"))
    )
    (net (code "85") (name "USB_DISC") (class "Default")
      (node (ref "R17") (pin "1") (pinfunction "1_1") (pintype "passive"))
      (node (ref "U4") (pin "53") (pinfunction "PC12_53") (pintype "bidirectional"))
    )
    (net (code "86") (name "USB_DM") (class "Default")
      (node (ref "C1") (pin "1") (pinfunction "1_1") (pintype "passive"))
      (node (ref "P4X") (pin "7") (pinfunction "7_7") (pintype "passive"))
      (node (ref "R16") (pin "1") (pinfunction "1_1") (pintype "passive"))
    )
    (net (code "87") (name "USB_DP") (class "Default")
      (node (ref "C2") (pin "1") (pinfunction "1_1") (pintype "passive"))
      (node (ref "P4X") (pin "1") (pinfunction "1_1") (pintype "passive"))
      (node (ref "R15") (pin "1") (pinfunction "1_1") (pintype "passive"))
      (node (ref "R21") (pin "1") (pinfunction "1_1") (pintype "passive"))
    )
    (net (code "88") (name "USB_PWREN") (class "Default")
      (node (ref "R14") (pin "2") (pinfunction "2_2") (pintype "passive"))
      (node (ref "R4") (pin "1") (pinfunction "1_1") (pintype "passive"))
      (node (ref "U4") (pin "52") (pinfunction "PC11_52") (pintype "bidirectional"))
    )
    (net (code "89") (name "USB_VBUS") (class "Default")
      (node (ref "C3") (pin "1") (pinfunction "1_1") (pintype "passive"))
      (node (ref "R19") (pin "2") (pinfunction "2_2") (pintype "passive"))
      (node (ref "R4") (pin "2") (pinfunction "2_2") (pintype "passive"))
      (node (ref "USB1X") (pin "1") (pinfunction "VCC_1") (pintype "power_in"))
    )
    (net (code "90") (name "VCAP") (class "Default")
      (node (ref "C20") (pin "1") (pinfunction "1_1") (pintype "passive"))
      (node (ref "U4") (pin "30") (pinfunction "VCAP1_30") (pintype "power_in"))
    )
    (net (code "91") (name "VDD") (class "Default")
      (node (ref "C16") (pin "1") (pinfunction "1_1") (pintype "passive"))
      (node (ref "C17") (pin "1") (pinfunction "1_1") (pintype "passive"))
      (node (ref "C18") (pin "1") (pinfunction "1_1") (pintype "passive"))
      (node (ref "C19") (pin "1") (pinfunction "1_1") (pintype "passive"))
      (node (ref "C22") (pin "1") (pinfunction "1_1") (pintype "passive"))
      (node (ref "C23") (pin "1") (pinfunction "1_1") (pintype "passive"))
      (node (ref "C24") (pin "1") (pinfunction "1_1") (pintype "passive"))
      (node (ref "C25") (pin "1") (pinfunction "1_1") (pintype "passive"))
      (node (ref "C26") (pin "1") (pinfunction "1_1") (pintype "passive"))
      (node (ref "C28") (pin "1") (pinfunction "1_1") (pintype "passive"))
      (node (ref "C5") (pin "1") (pinfunction "1_1") (pintype "passive"))
      (node (ref "J_ST") (pin "1") (pinfunction "VPP/MCLR_1") (pintype "passive"))
      (node (ref "L1") (pin "2") (pinfunction "2_2") (pintype "passive"))
      (node (ref "R1") (pin "2") (pinfunction "2_2") (pintype "passive"))
      (node (ref "R10") (pin "2") (pinfunction "2_2") (pintype "passive"))
      (node (ref "R2") (pin "1") (pinfunction "1_1") (pintype "passive"))
      (node (ref "R3") (pin "1") (pinfunction "1_1") (pintype "passive"))
      (node (ref "R6") (pin "1") (pinfunction "1_1") (pintype "passive"))
      (node (ref "R7") (pin "2") (pinfunction "2_2") (pintype "passive"))
      (node (ref "R9") (pin "1") (pinfunction "1_1") (pintype "passive"))
      (node (ref "U1") (pin "24") (pinfunction "VCC_24") (pintype "power_in"))
      (node (ref "U4") (pin "1") (pinfunction "VBAT_1") (pintype "power_in"))
      (node (ref "U4") (pin "19") (pinfunction "VDD_19") (pintype "power_in"))
      (node (ref "U4") (pin "32") (pinfunction "VDD_32") (pintype "power_in"))
      (node (ref "U4") (pin "48") (pinfunction "VDD_48") (pintype "power_in"))
      (node (ref "U4") (pin "64") (pinfunction "VDD_64") (pintype "power_in"))
      (node (ref "U5") (pin "5") (pinfunction "OUT_5") (pintype "passive"))
    )
    (net (code "92") (name "VDDA") (class "Default")
      (node (ref "C27") (pin "1") (pinfunction "1_1") (pintype "passive"))
      (node (ref "L1") (pin "1") (pinfunction "1_1") (pintype "passive"))
      (node (ref "U4") (pin "13") (pinfunction "VDDA/VREF+_13") (pintype "power_in"))
    )
    (net (code "93") (name "VIN_DC") (class "Default")
      (node (ref "C21") (pin "1") (pinfunction "1_1") (pintype "passive"))
      (node (ref "C9") (pin "1") (pinfunction "1_1") (pintype "passive"))
      (node (ref "P4X") (pin "2") (pinfunction "2_2") (pintype "passive"))
      (node (ref "PWR") (pin "PWR") (pinfunction "PWR_PWR") (pintype "bidirectional"))
      (node (ref "U3") (pin "3") (pinfunction "IN_3") (pintype "bidirectional"))
      (node (ref "U5") (pin "1") (pinfunction "IN_1") (pintype "input"))
      (node (ref "U5") (pin "3") (pinfunction "EN_3") (pintype "input"))
    )
    (net (code "94") (name "VXX") (class "Default")
      (node (ref "UART") (pin "3") (pinfunction "3_3") (pintype "bidirectional"))
    )
    (net (code "95") (name "unconnected-(J_ST-LVP-Pad6)") (class "Default")
      (node (ref "J_ST") (pin "6") (pinfunction "LVP_6") (pintype "bidirectional"))
    )
    (net (code "96") (name "unconnected-(MUX3X2-Pad1)") (class "Default")
      (node (ref "MUX3X2") (pin "1") (pinfunction "1_1") (pintype "passive"))
    )
    (net (code "97") (name "unconnected-(MUX3X2-Pad2)") (class "Default")
      (node (ref "MUX3X2") (pin "2") (pinfunction "2_2") (pintype "passive"))
    )
    (net (code "98") (name "unconnected-(MUX3X2-Pad3)") (class "Default")
      (node (ref "MUX3X2") (pin "3") (pinfunction "3_3") (pintype "passive"))
    )
    (net (code "99") (name "unconnected-(MUX3X2-Pad4)") (class "Default")
      (node (ref "MUX3X2") (pin "4") (pinfunction "4_4") (pintype "passive"))
    )
    (net (code "100") (name "unconnected-(MUX3X3-Pad1)") (class "Default")
      (node (ref "MUX3X3") (pin "1") (pinfunction "1_1") (pintype "passive"))
    )
    (net (code "101") (name "unconnected-(MUX3X3-Pad2)") (class "Default")
      (node (ref "MUX3X3") (pin "2") (pinfunction "2_2") (pintype "passive"))
    )
    (net (code "102") (name "unconnected-(MUX3X3-Pad3)") (class "Default")
      (node (ref "MUX3X3") (pin "3") (pinfunction "3_3") (pintype "passive"))
    )
    (net (code "103") (name "unconnected-(MUX3X3-Pad4)") (class "Default")
      (node (ref "MUX3X3") (pin "4") (pinfunction "4_4") (pintype "passive"))
    )
  )
)
